# GPU.net
KiCad netlist of a schematic drawn in EAGLE
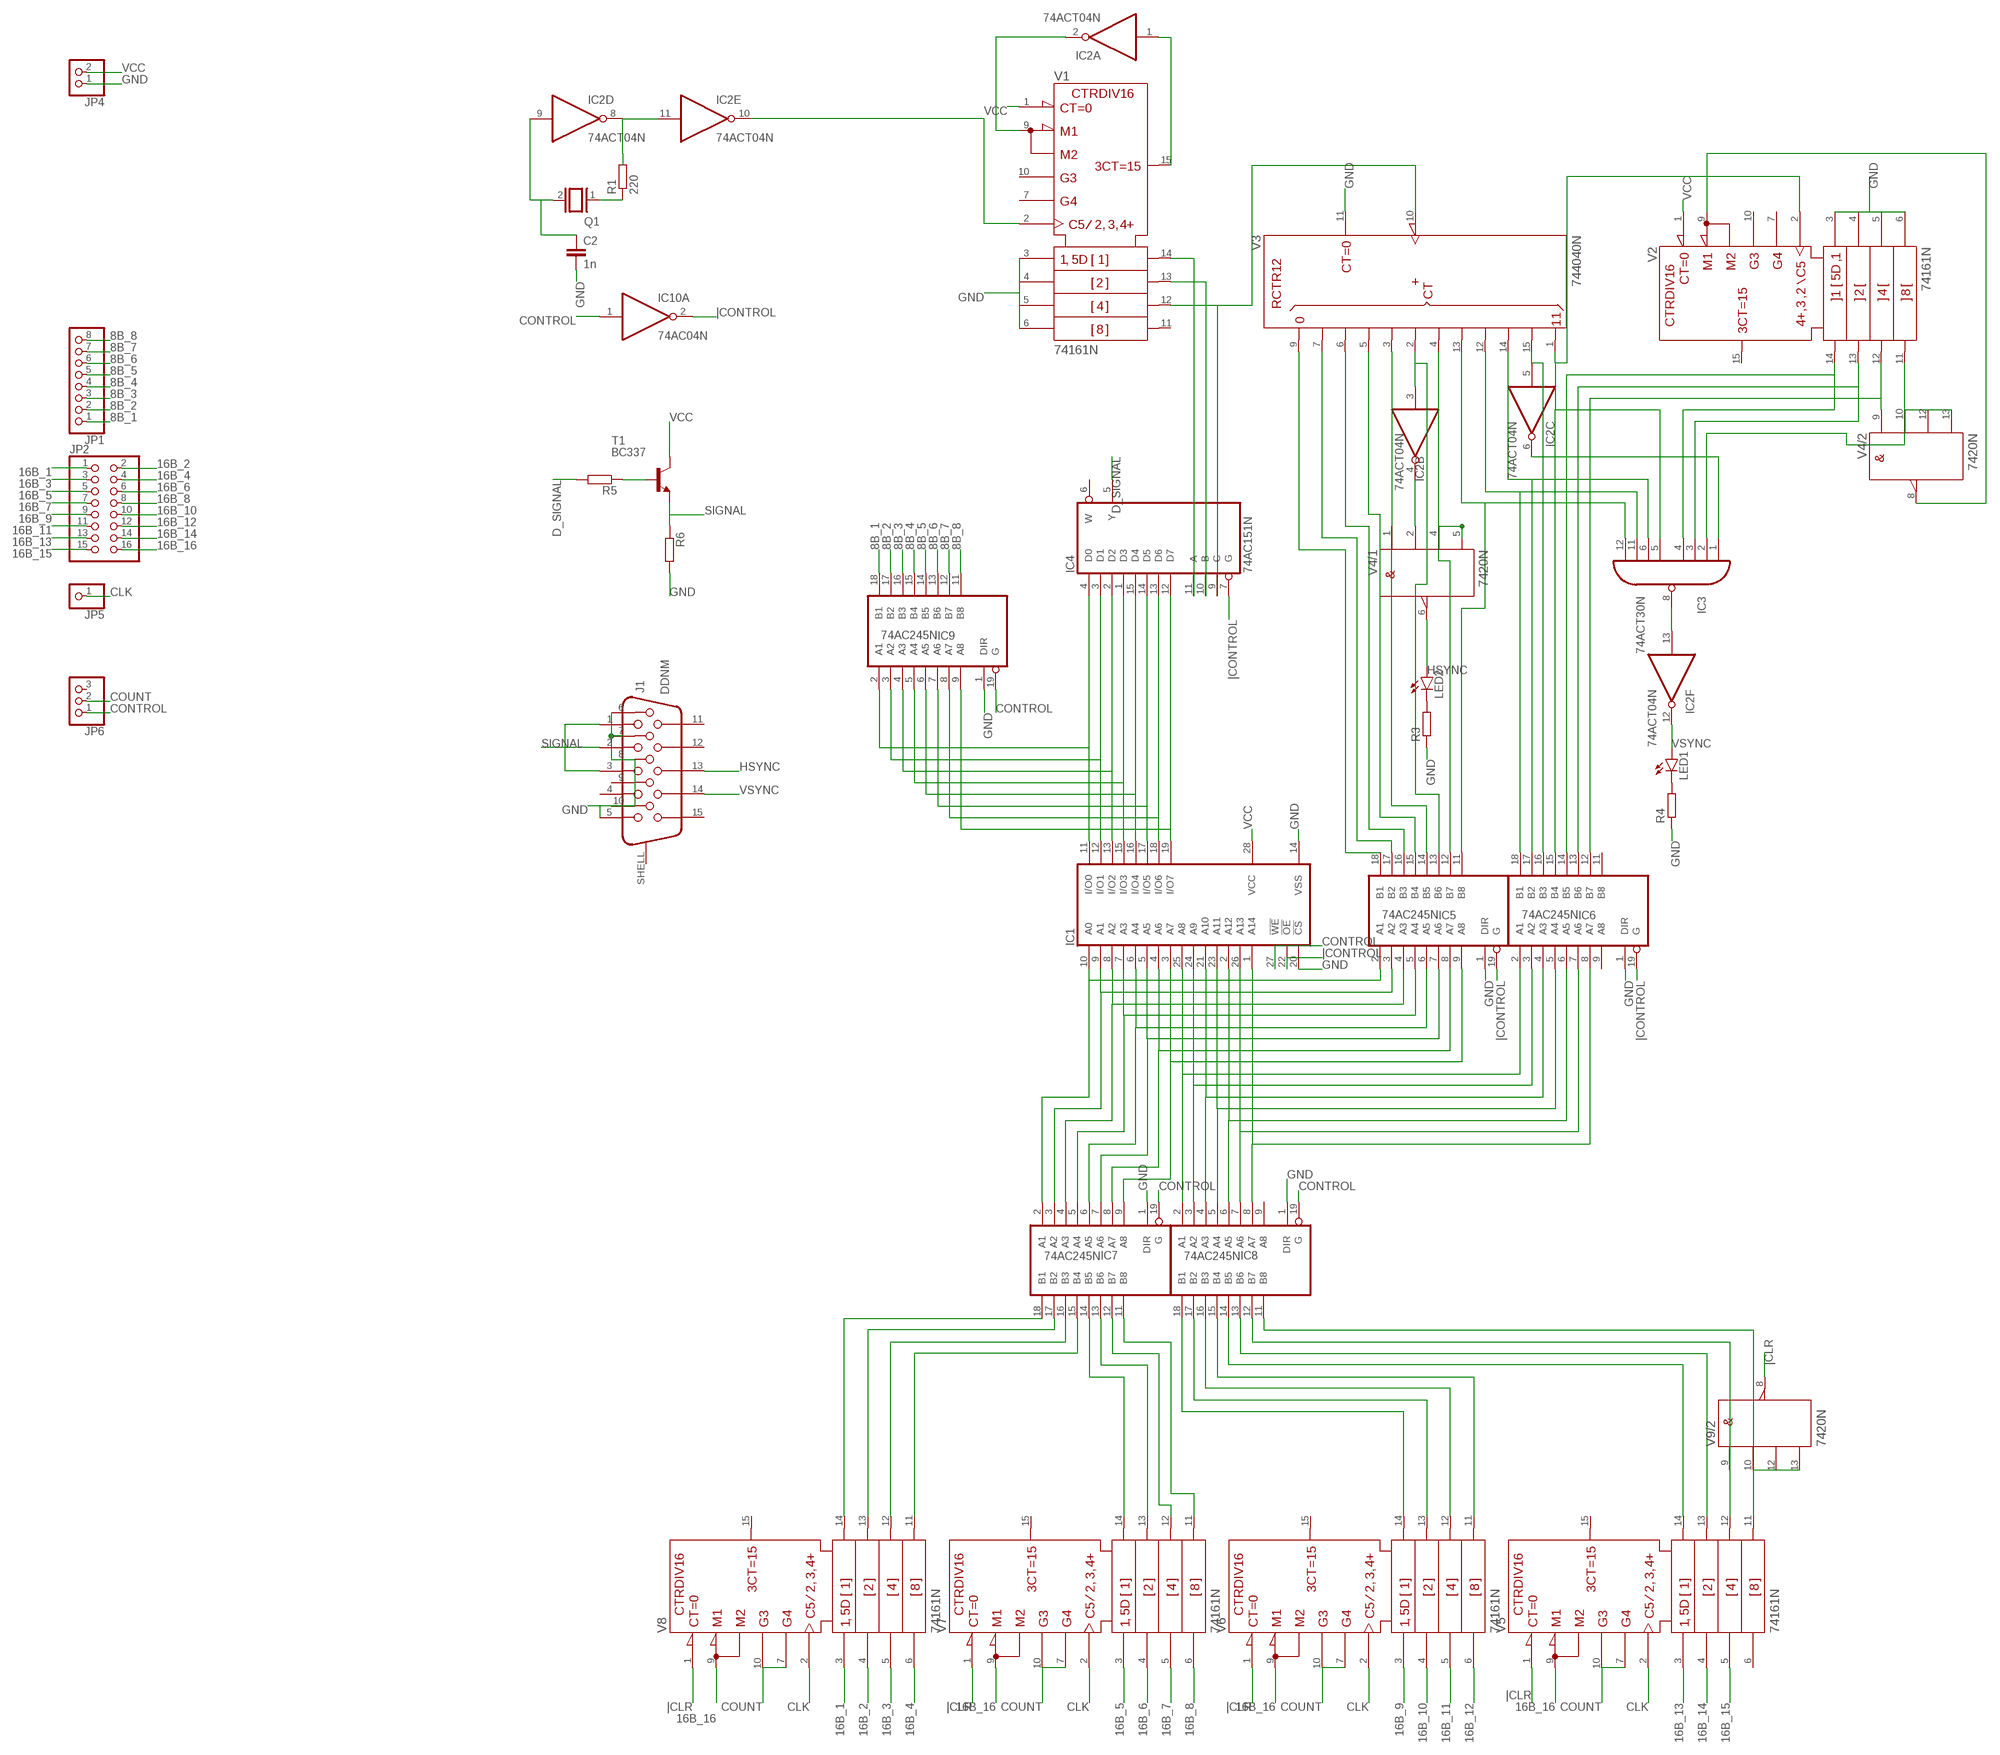
[diagram p0: schematic, sheet 1]

(export (version "E")
  (design (tool "Eeschema 10.0.6"))
  (components
    (comp (ref "C2")
      (value "1n")
      (footprint "eagle-import:C025-025X050")
      (libsource (lib "eagle-import") (part "C-EU025-025X050"))
    )
    (comp (ref "IC1")
      (value "62256P")
      (footprint "eagle-import:DIL28-6")
      (libsource (lib "eagle-import") (part "62256P"))
    )
    (comp (ref "IC2")
      (value "74ACT04N")
      (footprint "eagle-import:DIL14")
      (libsource (lib "eagle-import") (part "7404NACT"))
    )
    (comp (ref "IC3")
      (value "74ACT30N")
      (footprint "eagle-import:DIL14")
      (libsource (lib "eagle-import") (part "7430NACT"))
    )
    (comp (ref "IC4")
      (value "74AC151N")
      (footprint "eagle-import:DIL16")
      (libsource (lib "eagle-import") (part "74151NAC"))
    )
    (comp (ref "IC5")
      (value "74AC245N")
      (footprint "eagle-import:DIL20")
      (libsource (lib "eagle-import") (part "74245NAC"))
    )
    (comp (ref "IC6")
      (value "74AC245N")
      (footprint "eagle-import:DIL20")
      (libsource (lib "eagle-import") (part "74245NAC"))
    )
    (comp (ref "IC7")
      (value "74AC245N")
      (footprint "eagle-import:DIL20")
      (libsource (lib "eagle-import") (part "74245NAC"))
    )
    (comp (ref "IC8")
      (value "74AC245N")
      (footprint "eagle-import:DIL20")
      (libsource (lib "eagle-import") (part "74245NAC"))
    )
    (comp (ref "IC9")
      (value "74AC245N")
      (footprint "eagle-import:DIL20")
      (libsource (lib "eagle-import") (part "74245NAC"))
    )
    (comp (ref "IC10")
      (value "74AC04N")
      (footprint "eagle-import:DIL14")
      (libsource (lib "eagle-import") (part "7404NAC"))
    )
    (comp (ref "J1")
      (value "DDNM")
      (footprint "eagle-import:DNM")
      (fields (field (name "SPICEPREFIX") "X"))
      (libsource (lib "eagle-import") (part "DDNM"))
    )
    (comp (ref "JP1")
      (value "PINHD-1X8")
      (footprint "eagle-import:1X08")
      (libsource (lib "eagle-import") (part "PINHD-1X8"))
    )
    (comp (ref "JP2")
      (value "PINHD-2X8")
      (footprint "eagle-import:2X08")
      (libsource (lib "eagle-import") (part "PINHD-2X8"))
    )
    (comp (ref "JP4")
      (value "PINHD-1X2")
      (footprint "eagle-import:1X02")
      (libsource (lib "eagle-import") (part "PINHD-1X2"))
    )
    (comp (ref "JP5")
      (value "PINHD-1X1")
      (footprint "eagle-import:1X01")
      (libsource (lib "eagle-import") (part "PINHD-1X1"))
    )
    (comp (ref "JP6")
      (value "PINHD-1X3")
      (footprint "eagle-import:1X03")
      (libsource (lib "eagle-import") (part "PINHD-1X3"))
    )
    (comp (ref "LED1")
      (value "LED5MM")
      (footprint "eagle-import:LED5MM")
      (libsource (lib "eagle-import") (part "LED5MM"))
    )
    (comp (ref "LED2")
      (value "LED5MM")
      (footprint "eagle-import:LED5MM")
      (libsource (lib "eagle-import") (part "LED5MM"))
    )
    (comp (ref "Q1")
      (value "XTAL/S")
      (footprint "eagle-import:QS")
      (libsource (lib "eagle-import") (part "XTAL/S"))
    )
    (comp (ref "R1")
      (value "220")
      (footprint "eagle-import:0204_7")
      (libsource (lib "eagle-import") (part "R-EU_0204/7"))
    )
    (comp (ref "R3")
      (value "R-EU_0204/7")
      (footprint "eagle-import:0204_7")
      (libsource (lib "eagle-import") (part "R-EU_0204/7"))
    )
    (comp (ref "R4")
      (value "R-EU_0204/7")
      (footprint "eagle-import:0204_7")
      (libsource (lib "eagle-import") (part "R-EU_0204/7"))
    )
    (comp (ref "R5")
      (value "R-EU_0204/7")
      (footprint "eagle-import:0204_7")
      (libsource (lib "eagle-import") (part "resistor_348_R-EU_0204/7"))
    )
    (comp (ref "R6")
      (value "R-EU_0204/7")
      (footprint "eagle-import:0204_7")
      (libsource (lib "eagle-import") (part "resistor_348_R-EU_0204/7"))
    )
    (comp (ref "T1")
      (value "BC337")
      (footprint "eagle-import:TO92")
      (libsource (lib "eagle-import") (part "BC337"))
    )
    (comp (ref "V1")
      (value "74161N")
      (footprint "eagle-import:DIL16")
      (libsource (lib "eagle-import") (part "74161N"))
    )
    (comp (ref "V2")
      (value "74161N")
      (footprint "eagle-import:DIL16")
      (libsource (lib "eagle-import") (part "74161N"))
    )
    (comp (ref "V3")
      (value "744040N")
      (footprint "eagle-import:DIL16")
      (libsource (lib "eagle-import") (part "744040N"))
    )
    (comp (ref "V4")
      (value "7420N")
      (footprint "eagle-import:DIL14")
      (libsource (lib "eagle-import") (part "7420N"))
    )
    (comp (ref "V5")
      (value "74161N")
      (footprint "eagle-import:DIL16")
      (libsource (lib "eagle-import") (part "74161N"))
    )
    (comp (ref "V6")
      (value "74161N")
      (footprint "eagle-import:DIL16")
      (libsource (lib "eagle-import") (part "74161N"))
    )
    (comp (ref "V7")
      (value "74161N")
      (footprint "eagle-import:DIL16")
      (libsource (lib "eagle-import") (part "74161N"))
    )
    (comp (ref "V8")
      (value "74161N")
      (footprint "eagle-import:DIL16")
      (libsource (lib "eagle-import") (part "74161N"))
    )
    (comp (ref "V9")
      (value "7420N")
      (footprint "eagle-import:DIL14")
      (libsource (lib "eagle-import") (part "7420N"))
    )
  )
  (nets
    (net (code "1") (name "/8B_1") (class "Default")
      (node (ref "IC9") (pin "18") (pinfunction "B1_18") (pintype "bidirectional"))
      (node (ref "JP1") (pin "1") (pinfunction "1_1") (pintype "passive"))
    )
    (net (code "2") (name "/8B_2") (class "Default")
      (node (ref "IC9") (pin "17") (pinfunction "B2_17") (pintype "bidirectional"))
      (node (ref "JP1") (pin "2") (pinfunction "2_2") (pintype "passive"))
    )
    (net (code "3") (name "/8B_3") (class "Default")
      (node (ref "IC9") (pin "16") (pinfunction "B3_16") (pintype "bidirectional"))
      (node (ref "JP1") (pin "3") (pinfunction "3_3") (pintype "passive"))
    )
    (net (code "4") (name "/8B_4") (class "Default")
      (node (ref "IC9") (pin "15") (pinfunction "B4_15") (pintype "bidirectional"))
      (node (ref "JP1") (pin "4") (pinfunction "4_4") (pintype "passive"))
    )
    (net (code "5") (name "/8B_5") (class "Default")
      (node (ref "IC9") (pin "14") (pinfunction "B5_14") (pintype "bidirectional"))
      (node (ref "JP1") (pin "5") (pinfunction "5_5") (pintype "passive"))
    )
    (net (code "6") (name "/8B_6") (class "Default")
      (node (ref "IC9") (pin "13") (pinfunction "B6_13") (pintype "bidirectional"))
      (node (ref "JP1") (pin "6") (pinfunction "6_6") (pintype "passive"))
    )
    (net (code "7") (name "/8B_7") (class "Default")
      (node (ref "IC9") (pin "12") (pinfunction "B7_12") (pintype "bidirectional"))
      (node (ref "JP1") (pin "7") (pinfunction "7_7") (pintype "passive"))
    )
    (net (code "8") (name "/8B_8") (class "Default")
      (node (ref "IC9") (pin "11") (pinfunction "B8_11") (pintype "bidirectional"))
      (node (ref "JP1") (pin "8") (pinfunction "8_8") (pintype "passive"))
    )
    (net (code "9") (name "/16B_1") (class "Default")
      (node (ref "JP2") (pin "1") (pinfunction "1_1") (pintype "passive"))
      (node (ref "V8") (pin "3") (pinfunction "A_3") (pintype "input"))
    )
    (net (code "10") (name "/16B_2") (class "Default")
      (node (ref "JP2") (pin "2") (pinfunction "2_2") (pintype "passive"))
      (node (ref "V8") (pin "4") (pinfunction "B_4") (pintype "input"))
    )
    (net (code "11") (name "/16B_3") (class "Default")
      (node (ref "JP2") (pin "3") (pinfunction "3_3") (pintype "passive"))
      (node (ref "V8") (pin "5") (pinfunction "C_5") (pintype "input"))
    )
    (net (code "12") (name "/16B_4") (class "Default")
      (node (ref "JP2") (pin "4") (pinfunction "4_4") (pintype "passive"))
      (node (ref "V8") (pin "6") (pinfunction "D_6") (pintype "input"))
    )
    (net (code "13") (name "/16B_5") (class "Default")
      (node (ref "JP2") (pin "5") (pinfunction "5_5") (pintype "passive"))
      (node (ref "V7") (pin "3") (pinfunction "A_3") (pintype "input"))
    )
    (net (code "14") (name "/16B_6") (class "Default")
      (node (ref "JP2") (pin "6") (pinfunction "6_6") (pintype "passive"))
      (node (ref "V7") (pin "4") (pinfunction "B_4") (pintype "input"))
    )
    (net (code "15") (name "/16B_7") (class "Default")
      (node (ref "JP2") (pin "7") (pinfunction "7_7") (pintype "passive"))
      (node (ref "V7") (pin "5") (pinfunction "C_5") (pintype "input"))
    )
    (net (code "16") (name "/16B_8") (class "Default")
      (node (ref "JP2") (pin "8") (pinfunction "8_8") (pintype "passive"))
      (node (ref "V7") (pin "6") (pinfunction "D_6") (pintype "input"))
    )
    (net (code "17") (name "/16B_9") (class "Default")
      (node (ref "JP2") (pin "9") (pinfunction "9_9") (pintype "passive"))
      (node (ref "V6") (pin "3") (pinfunction "A_3") (pintype "input"))
    )
    (net (code "18") (name "/16B_10") (class "Default")
      (node (ref "JP2") (pin "10") (pinfunction "10_10") (pintype "passive"))
      (node (ref "V6") (pin "4") (pinfunction "B_4") (pintype "input"))
    )
    (net (code "19") (name "/16B_11") (class "Default")
      (node (ref "JP2") (pin "11") (pinfunction "11_11") (pintype "passive"))
      (node (ref "V6") (pin "5") (pinfunction "C_5") (pintype "input"))
    )
    (net (code "20") (name "/16B_12") (class "Default")
      (node (ref "JP2") (pin "12") (pinfunction "12_12") (pintype "passive"))
      (node (ref "V6") (pin "6") (pinfunction "D_6") (pintype "input"))
    )
    (net (code "21") (name "/16B_13") (class "Default")
      (node (ref "JP2") (pin "13") (pinfunction "13_13") (pintype "passive"))
      (node (ref "V5") (pin "3") (pinfunction "A_3") (pintype "input"))
    )
    (net (code "22") (name "/16B_14") (class "Default")
      (node (ref "JP2") (pin "14") (pinfunction "14_14") (pintype "passive"))
      (node (ref "V5") (pin "4") (pinfunction "B_4") (pintype "input"))
    )
    (net (code "23") (name "/16B_15") (class "Default")
      (node (ref "JP2") (pin "15") (pinfunction "15_15") (pintype "passive"))
      (node (ref "V5") (pin "5") (pinfunction "C_5") (pintype "input"))
    )
    (net (code "24") (name "/16B_16") (class "Default")
      (node (ref "JP2") (pin "16") (pinfunction "16_16") (pintype "passive"))
      (node (ref "V5") (pin "9") (pinfunction "~{LOAD}_9") (pintype "input"))
      (node (ref "V6") (pin "9") (pinfunction "~{LOAD}_9") (pintype "input"))
      (node (ref "V7") (pin "9") (pinfunction "~{LOAD}_9") (pintype "input"))
      (node (ref "V8") (pin "9") (pinfunction "~{LOAD}_9") (pintype "input"))
    )
    (net (code "25") (name "/CLK") (class "Default")
      (node (ref "JP5") (pin "1") (pinfunction "1_1") (pintype "passive"))
      (node (ref "V5") (pin "2") (pinfunction "CLK_2") (pintype "input"))
      (node (ref "V6") (pin "2") (pinfunction "CLK_2") (pintype "input"))
      (node (ref "V7") (pin "2") (pinfunction "CLK_2") (pintype "input"))
      (node (ref "V8") (pin "2") (pinfunction "CLK_2") (pintype "input"))
    )
    (net (code "26") (name "/CONTROL") (class "Default")
      (node (ref "IC1") (pin "27") (pinfunction "~{WE}_27") (pintype "input"))
      (node (ref "IC10") (pin "1") (pinfunction "I_1") (pintype "input"))
      (node (ref "IC7") (pin "19") (pinfunction "G_19") (pintype "input"))
      (node (ref "IC8") (pin "19") (pinfunction "G_19") (pintype "input"))
      (node (ref "IC9") (pin "19") (pinfunction "G_19") (pintype "input"))
      (node (ref "JP6") (pin "1") (pinfunction "1_1") (pintype "passive"))
    )
    (net (code "27") (name "/COUNT") (class "Default")
      (node (ref "JP6") (pin "2") (pinfunction "2_2") (pintype "passive"))
      (node (ref "V5") (pin "10") (pinfunction "ENT_10") (pintype "input"))
      (node (ref "V5") (pin "7") (pinfunction "ENP_7") (pintype "input"))
      (node (ref "V6") (pin "10") (pinfunction "ENT_10") (pintype "input"))
      (node (ref "V6") (pin "7") (pinfunction "ENP_7") (pintype "input"))
      (node (ref "V7") (pin "10") (pinfunction "ENT_10") (pintype "input"))
      (node (ref "V7") (pin "7") (pinfunction "ENP_7") (pintype "input"))
      (node (ref "V8") (pin "10") (pinfunction "ENT_10") (pintype "input"))
      (node (ref "V8") (pin "7") (pinfunction "ENP_7") (pintype "input"))
    )
    (net (code "28") (name "/D_SIGNAL") (class "Default")
      (node (ref "IC4") (pin "5") (pinfunction "Y_5") (pintype "output"))
      (node (ref "R5") (pin "2") (pinfunction "2_2") (pintype "passive"))
    )
    (net (code "29") (name "/GND") (class "Default")
      (node (ref "C2") (pin "2") (pinfunction "2_2") (pintype "passive"))
      (node (ref "IC1") (pin "14") (pinfunction "VSS_14") (pintype "power_in"))
      (node (ref "IC1") (pin "20") (pinfunction "~{CS}_20") (pintype "input"))
      (node (ref "IC5") (pin "1") (pinfunction "DIR_1") (pintype "input"))
      (node (ref "IC6") (pin "1") (pinfunction "DIR_1") (pintype "input"))
      (node (ref "IC7") (pin "1") (pinfunction "DIR_1") (pintype "input"))
      (node (ref "IC8") (pin "1") (pinfunction "DIR_1") (pintype "input"))
      (node (ref "IC9") (pin "1") (pinfunction "DIR_1") (pintype "input"))
      (node (ref "J1") (pin "10") (pinfunction "10_10") (pintype "bidirectional"))
      (node (ref "J1") (pin "5") (pinfunction "5_5") (pintype "bidirectional"))
      (node (ref "J1") (pin "6") (pinfunction "6_6") (pintype "bidirectional"))
      (node (ref "J1") (pin "7") (pinfunction "7_7") (pintype "bidirectional"))
      (node (ref "J1") (pin "8") (pinfunction "8_8") (pintype "bidirectional"))
      (node (ref "JP4") (pin "1") (pinfunction "1_1") (pintype "passive"))
      (node (ref "R3") (pin "1") (pinfunction "1_1") (pintype "passive"))
      (node (ref "R4") (pin "1") (pinfunction "1_1") (pintype "passive"))
      (node (ref "R6") (pin "2") (pinfunction "2_2") (pintype "passive"))
      (node (ref "V1") (pin "3") (pinfunction "A_3") (pintype "input"))
      (node (ref "V1") (pin "4") (pinfunction "B_4") (pintype "input"))
      (node (ref "V1") (pin "5") (pinfunction "C_5") (pintype "input"))
      (node (ref "V1") (pin "6") (pinfunction "D_6") (pintype "input"))
      (node (ref "V2") (pin "3") (pinfunction "A_3") (pintype "input"))
      (node (ref "V2") (pin "4") (pinfunction "B_4") (pintype "input"))
      (node (ref "V2") (pin "5") (pinfunction "C_5") (pintype "input"))
      (node (ref "V2") (pin "6") (pinfunction "D_6") (pintype "input"))
      (node (ref "V3") (pin "11") (pinfunction "CLR_11") (pintype "input"))
    )
    (net (code "30") (name "/HSYNC") (class "Default")
      (node (ref "J1") (pin "13") (pinfunction "13_13") (pintype "bidirectional"))
      (node (ref "LED2") (pin "A") (pinfunction "A_A") (pintype "passive"))
      (node (ref "V4") (pin "6") (pinfunction "Y_6") (pintype "output"))
    )
    (net (code "31") (name "/SIGNAL") (class "Default")
      (node (ref "J1") (pin "1") (pinfunction "1_1") (pintype "bidirectional"))
      (node (ref "J1") (pin "2") (pinfunction "2_2") (pintype "bidirectional"))
      (node (ref "J1") (pin "3") (pinfunction "3_3") (pintype "bidirectional"))
      (node (ref "R6") (pin "1") (pinfunction "1_1") (pintype "passive"))
      (node (ref "T1") (pin "1") (pinfunction "E_1") (pintype "passive"))
    )
    (net (code "32") (name "/VCC") (class "Default")
      (node (ref "IC1") (pin "28") (pinfunction "VCC_28") (pintype "power_in"))
      (node (ref "JP4") (pin "2") (pinfunction "2_2") (pintype "passive"))
      (node (ref "T1") (pin "3") (pinfunction "C_3") (pintype "passive"))
      (node (ref "V1") (pin "1") (pinfunction "~{CLR}_1") (pintype "input"))
      (node (ref "V2") (pin "1") (pinfunction "~{CLR}_1") (pintype "input"))
    )
    (net (code "33") (name "/VSYNC") (class "Default")
      (node (ref "IC2") (pin "12") (pinfunction "O_12") (pintype "output"))
      (node (ref "J1") (pin "14") (pinfunction "14_14") (pintype "bidirectional"))
      (node (ref "LED1") (pin "A") (pinfunction "A_A") (pintype "passive"))
    )
    (net (code "34") (name "/|CLR") (class "Default")
      (node (ref "V5") (pin "1") (pinfunction "~{CLR}_1") (pintype "input"))
      (node (ref "V6") (pin "1") (pinfunction "~{CLR}_1") (pintype "input"))
      (node (ref "V7") (pin "1") (pinfunction "~{CLR}_1") (pintype "input"))
      (node (ref "V8") (pin "1") (pinfunction "~{CLR}_1") (pintype "input"))
      (node (ref "V9") (pin "8") (pinfunction "Y_8") (pintype "output"))
    )
    (net (code "35") (name "/|CONTROL") (class "Default")
      (node (ref "IC1") (pin "22") (pinfunction "~{OE}_22") (pintype "input"))
      (node (ref "IC10") (pin "2") (pinfunction "O_2") (pintype "output"))
      (node (ref "IC4") (pin "7") (pinfunction "G_7") (pintype "input"))
      (node (ref "IC5") (pin "19") (pinfunction "G_19") (pintype "input"))
      (node (ref "IC6") (pin "19") (pinfunction "G_19") (pintype "input"))
    )
    (net (code "36") (name "Net-(IC1-A0)") (class "Default")
      (node (ref "IC1") (pin "10") (pinfunction "A0_10") (pintype "input"))
      (node (ref "IC5") (pin "2") (pinfunction "A1_2") (pintype "bidirectional"))
      (node (ref "IC7") (pin "2") (pinfunction "A1_2") (pintype "bidirectional"))
    )
    (net (code "37") (name "Net-(IC1-A1)") (class "Default")
      (node (ref "IC1") (pin "9") (pinfunction "A1_9") (pintype "input"))
      (node (ref "IC5") (pin "3") (pinfunction "A2_3") (pintype "bidirectional"))
      (node (ref "IC7") (pin "3") (pinfunction "A2_3") (pintype "bidirectional"))
    )
    (net (code "38") (name "Net-(IC1-A2)") (class "Default")
      (node (ref "IC1") (pin "8") (pinfunction "A2_8") (pintype "input"))
      (node (ref "IC5") (pin "4") (pinfunction "A3_4") (pintype "bidirectional"))
      (node (ref "IC7") (pin "4") (pinfunction "A3_4") (pintype "bidirectional"))
    )
    (net (code "39") (name "Net-(IC1-A3)") (class "Default")
      (node (ref "IC1") (pin "7") (pinfunction "A3_7") (pintype "input"))
      (node (ref "IC5") (pin "5") (pinfunction "A4_5") (pintype "bidirectional"))
      (node (ref "IC7") (pin "5") (pinfunction "A4_5") (pintype "bidirectional"))
    )
    (net (code "40") (name "Net-(IC1-A4)") (class "Default")
      (node (ref "IC1") (pin "6") (pinfunction "A4_6") (pintype "input"))
      (node (ref "IC5") (pin "6") (pinfunction "A5_6") (pintype "bidirectional"))
      (node (ref "IC7") (pin "6") (pinfunction "A5_6") (pintype "bidirectional"))
    )
    (net (code "41") (name "Net-(IC1-A5)") (class "Default")
      (node (ref "IC1") (pin "5") (pinfunction "A5_5") (pintype "input"))
      (node (ref "IC5") (pin "7") (pinfunction "A6_7") (pintype "bidirectional"))
      (node (ref "IC7") (pin "7") (pinfunction "A6_7") (pintype "bidirectional"))
    )
    (net (code "42") (name "Net-(IC1-A6)") (class "Default")
      (node (ref "IC1") (pin "4") (pinfunction "A6_4") (pintype "input"))
      (node (ref "IC5") (pin "8") (pinfunction "A7_8") (pintype "bidirectional"))
      (node (ref "IC7") (pin "8") (pinfunction "A7_8") (pintype "bidirectional"))
    )
    (net (code "43") (name "Net-(IC1-A7)") (class "Default")
      (node (ref "IC1") (pin "3") (pinfunction "A7_3") (pintype "input"))
      (node (ref "IC5") (pin "9") (pinfunction "A8_9") (pintype "bidirectional"))
      (node (ref "IC7") (pin "9") (pinfunction "A8_9") (pintype "bidirectional"))
    )
    (net (code "44") (name "Net-(IC1-A8)") (class "Default")
      (node (ref "IC1") (pin "25") (pinfunction "A8_25") (pintype "input"))
      (node (ref "IC6") (pin "2") (pinfunction "A1_2") (pintype "bidirectional"))
      (node (ref "IC8") (pin "2") (pinfunction "A1_2") (pintype "bidirectional"))
    )
    (net (code "45") (name "Net-(IC1-A9)") (class "Default")
      (node (ref "IC1") (pin "24") (pinfunction "A9_24") (pintype "input"))
      (node (ref "IC6") (pin "3") (pinfunction "A2_3") (pintype "bidirectional"))
      (node (ref "IC8") (pin "3") (pinfunction "A2_3") (pintype "bidirectional"))
    )
    (net (code "46") (name "Net-(IC1-A10)") (class "Default")
      (node (ref "IC1") (pin "21") (pinfunction "A10_21") (pintype "input"))
      (node (ref "IC6") (pin "4") (pinfunction "A3_4") (pintype "bidirectional"))
      (node (ref "IC8") (pin "4") (pinfunction "A3_4") (pintype "bidirectional"))
    )
    (net (code "47") (name "Net-(IC1-A11)") (class "Default")
      (node (ref "IC1") (pin "23") (pinfunction "A11_23") (pintype "input"))
      (node (ref "IC6") (pin "5") (pinfunction "A4_5") (pintype "bidirectional"))
      (node (ref "IC8") (pin "5") (pinfunction "A4_5") (pintype "bidirectional"))
    )
    (net (code "48") (name "Net-(IC1-A12)") (class "Default")
      (node (ref "IC1") (pin "2") (pinfunction "A12_2") (pintype "input"))
      (node (ref "IC6") (pin "6") (pinfunction "A5_6") (pintype "bidirectional"))
      (node (ref "IC8") (pin "6") (pinfunction "A5_6") (pintype "bidirectional"))
    )
    (net (code "49") (name "Net-(IC1-A13)") (class "Default")
      (node (ref "IC1") (pin "26") (pinfunction "A13_26") (pintype "input"))
      (node (ref "IC6") (pin "7") (pinfunction "A6_7") (pintype "bidirectional"))
      (node (ref "IC8") (pin "7") (pinfunction "A6_7") (pintype "bidirectional"))
    )
    (net (code "50") (name "Net-(IC1-A14)") (class "Default")
      (node (ref "IC1") (pin "1") (pinfunction "A14_1") (pintype "input"))
      (node (ref "IC6") (pin "8") (pinfunction "A7_8") (pintype "bidirectional"))
      (node (ref "IC8") (pin "8") (pinfunction "A7_8") (pintype "bidirectional"))
    )
    (net (code "51") (name "Net-(IC1-I{slash}O0)") (class "Default")
      (node (ref "IC1") (pin "11") (pinfunction "I/O0_11") (pintype "bidirectional"))
      (node (ref "IC4") (pin "4") (pinfunction "D0_4") (pintype "input"))
      (node (ref "IC9") (pin "2") (pinfunction "A1_2") (pintype "bidirectional"))
    )
    (net (code "52") (name "Net-(IC1-I{slash}O1)") (class "Default")
      (node (ref "IC1") (pin "12") (pinfunction "I/O1_12") (pintype "bidirectional"))
      (node (ref "IC4") (pin "3") (pinfunction "D1_3") (pintype "input"))
      (node (ref "IC9") (pin "3") (pinfunction "A2_3") (pintype "bidirectional"))
    )
    (net (code "53") (name "Net-(IC1-I{slash}O2)") (class "Default")
      (node (ref "IC1") (pin "13") (pinfunction "I/O2_13") (pintype "bidirectional"))
      (node (ref "IC4") (pin "2") (pinfunction "D2_2") (pintype "input"))
      (node (ref "IC9") (pin "4") (pinfunction "A3_4") (pintype "bidirectional"))
    )
    (net (code "54") (name "Net-(IC1-I{slash}O3)") (class "Default")
      (node (ref "IC1") (pin "15") (pinfunction "I/O3_15") (pintype "bidirectional"))
      (node (ref "IC4") (pin "1") (pinfunction "D3_1") (pintype "input"))
      (node (ref "IC9") (pin "5") (pinfunction "A4_5") (pintype "bidirectional"))
    )
    (net (code "55") (name "Net-(IC1-I{slash}O4)") (class "Default")
      (node (ref "IC1") (pin "16") (pinfunction "I/O4_16") (pintype "bidirectional"))
      (node (ref "IC4") (pin "15") (pinfunction "D4_15") (pintype "input"))
      (node (ref "IC9") (pin "6") (pinfunction "A5_6") (pintype "bidirectional"))
    )
    (net (code "56") (name "Net-(IC1-I{slash}O5)") (class "Default")
      (node (ref "IC1") (pin "17") (pinfunction "I/O5_17") (pintype "bidirectional"))
      (node (ref "IC4") (pin "14") (pinfunction "D5_14") (pintype "input"))
      (node (ref "IC9") (pin "7") (pinfunction "A6_7") (pintype "bidirectional"))
    )
    (net (code "57") (name "Net-(IC1-I{slash}O6)") (class "Default")
      (node (ref "IC1") (pin "18") (pinfunction "I/O6_18") (pintype "bidirectional"))
      (node (ref "IC4") (pin "13") (pinfunction "D6_13") (pintype "input"))
      (node (ref "IC9") (pin "8") (pinfunction "A7_8") (pintype "bidirectional"))
    )
    (net (code "58") (name "Net-(IC1-I{slash}O7)") (class "Default")
      (node (ref "IC1") (pin "19") (pinfunction "I/O7_19") (pintype "bidirectional"))
      (node (ref "IC4") (pin "12") (pinfunction "D7_12") (pintype "input"))
      (node (ref "IC9") (pin "9") (pinfunction "A8_9") (pintype "bidirectional"))
    )
    (net (code "59") (name "Net-(IC2A-I)") (class "Default")
      (node (ref "IC2") (pin "1") (pinfunction "I_1") (pintype "input"))
      (node (ref "V1") (pin "15") (pinfunction "RCO_15") (pintype "output"))
    )
    (net (code "60") (name "Net-(IC2A-O)") (class "Default")
      (node (ref "IC2") (pin "2") (pinfunction "O_2") (pintype "output"))
      (node (ref "V1") (pin "9") (pinfunction "~{LOAD}_9") (pintype "input"))
    )
    (net (code "61") (name "Net-(IC2B-I)") (class "Default")
      (node (ref "IC2") (pin "3") (pinfunction "I_3") (pintype "input"))
      (node (ref "IC5") (pin "13") (pinfunction "B6_13") (pintype "bidirectional"))
      (node (ref "V3") (pin "2") (pinfunction "QF_2") (pintype "output"))
    )
    (net (code "62") (name "Net-(IC2B-O)") (class "Default")
      (node (ref "IC2") (pin "4") (pinfunction "O_4") (pintype "output"))
      (node (ref "V4") (pin "2") (pinfunction "B_2") (pintype "input"))
    )
    (net (code "63") (name "Net-(IC2C-I)") (class "Default")
      (node (ref "IC2") (pin "5") (pinfunction "I_5") (pintype "input"))
      (node (ref "IC6") (pin "16") (pinfunction "B3_16") (pintype "bidirectional"))
      (node (ref "V3") (pin "15") (pinfunction "QK_15") (pintype "output"))
    )
    (net (code "64") (name "Net-(IC2C-O)") (class "Default")
      (node (ref "IC2") (pin "6") (pinfunction "O_6") (pintype "output"))
      (node (ref "IC3") (pin "1") (pinfunction "I0_1") (pintype "input"))
    )
    (net (code "65") (name "Net-(IC2D-I)") (class "Default")
      (node (ref "C2") (pin "1") (pinfunction "1_1") (pintype "passive"))
      (node (ref "IC2") (pin "9") (pinfunction "I_9") (pintype "input"))
      (node (ref "Q1") (pin "2") (pinfunction "2_2") (pintype "passive"))
    )
    (net (code "66") (name "Net-(IC2D-O)") (class "Default")
      (node (ref "IC2") (pin "11") (pinfunction "I_11") (pintype "input"))
      (node (ref "IC2") (pin "8") (pinfunction "O_8") (pintype "output"))
      (node (ref "R1") (pin "2") (pinfunction "2_2") (pintype "passive"))
    )
    (net (code "67") (name "Net-(IC2E-O)") (class "Default")
      (node (ref "IC2") (pin "10") (pinfunction "O_10") (pintype "output"))
      (node (ref "V1") (pin "2") (pinfunction "CLK_2") (pintype "input"))
    )
    (net (code "68") (name "Net-(IC2F-I)") (class "Default")
      (node (ref "IC2") (pin "13") (pinfunction "I_13") (pintype "input"))
      (node (ref "IC3") (pin "8") (pinfunction "O_8") (pintype "output"))
    )
    (net (code "69") (name "Net-(IC3A-I1)") (class "Default")
      (node (ref "IC3") (pin "2") (pinfunction "I1_2") (pintype "input"))
      (node (ref "V2") (pin "11") (pinfunction "QD_11") (pintype "output"))
      (node (ref "V4") (pin "10") (pinfunction "B_10") (pintype "input"))
      (node (ref "V4") (pin "12") (pinfunction "C_12") (pintype "input"))
      (node (ref "V4") (pin "13") (pinfunction "D_13") (pintype "input"))
    )
    (net (code "70") (name "Net-(IC3A-I2)") (class "Default")
      (node (ref "IC3") (pin "3") (pinfunction "I2_3") (pintype "input"))
      (node (ref "IC6") (pin "13") (pinfunction "B6_13") (pintype "bidirectional"))
      (node (ref "V2") (pin "13") (pinfunction "QB_13") (pintype "output"))
    )
    (net (code "71") (name "Net-(IC3A-I3)") (class "Default")
      (node (ref "IC3") (pin "4") (pinfunction "I3_4") (pintype "input"))
      (node (ref "IC6") (pin "14") (pinfunction "B5_14") (pintype "bidirectional"))
      (node (ref "V2") (pin "14") (pinfunction "QA_14") (pintype "output"))
    )
    (net (code "72") (name "Net-(IC3A-I4)") (class "Default")
      (node (ref "IC3") (pin "5") (pinfunction "I4_5") (pintype "input"))
      (node (ref "IC6") (pin "15") (pinfunction "B4_15") (pintype "bidirectional"))
      (node (ref "V2") (pin "2") (pinfunction "CLK_2") (pintype "input"))
      (node (ref "V3") (pin "1") (pinfunction "QL_1") (pintype "output"))
    )
    (net (code "73") (name "Net-(IC3A-I5)") (class "Default")
      (node (ref "IC3") (pin "6") (pinfunction "I5_6") (pintype "input"))
      (node (ref "IC6") (pin "17") (pinfunction "B2_17") (pintype "bidirectional"))
      (node (ref "V3") (pin "14") (pinfunction "QJ_14") (pintype "output"))
    )
    (net (code "74") (name "Net-(IC3A-I6)") (class "Default")
      (node (ref "IC3") (pin "11") (pinfunction "I6_11") (pintype "input"))
      (node (ref "IC6") (pin "18") (pinfunction "B1_18") (pintype "bidirectional"))
      (node (ref "V3") (pin "12") (pinfunction "QI_12") (pintype "output"))
    )
    (net (code "75") (name "Net-(IC3A-I7)") (class "Default")
      (node (ref "IC3") (pin "12") (pinfunction "I7_12") (pintype "input"))
      (node (ref "IC5") (pin "11") (pinfunction "B8_11") (pintype "bidirectional"))
      (node (ref "V3") (pin "13") (pinfunction "QH_13") (pintype "output"))
    )
    (net (code "76") (name "Net-(IC4A-A)") (class "Default")
      (node (ref "IC4") (pin "11") (pinfunction "A_11") (pintype "input"))
      (node (ref "V1") (pin "14") (pinfunction "QA_14") (pintype "output"))
    )
    (net (code "77") (name "Net-(IC4A-B)") (class "Default")
      (node (ref "IC4") (pin "10") (pinfunction "B_10") (pintype "input"))
      (node (ref "V1") (pin "13") (pinfunction "QB_13") (pintype "output"))
    )
    (net (code "78") (name "Net-(IC4A-C)") (class "Default")
      (node (ref "IC4") (pin "9") (pinfunction "C_9") (pintype "input"))
      (node (ref "V1") (pin "12") (pinfunction "QC_12") (pintype "output"))
      (node (ref "V3") (pin "10") (pinfunction "CLK_10") (pintype "input"))
    )
    (net (code "79") (name "Net-(IC5A-B1)") (class "Default")
      (node (ref "IC5") (pin "18") (pinfunction "B1_18") (pintype "bidirectional"))
      (node (ref "V3") (pin "9") (pinfunction "QA_9") (pintype "output"))
    )
    (net (code "80") (name "Net-(IC5A-B2)") (class "Default")
      (node (ref "IC5") (pin "17") (pinfunction "B2_17") (pintype "bidirectional"))
      (node (ref "V3") (pin "7") (pinfunction "QB_7") (pintype "output"))
    )
    (net (code "81") (name "Net-(IC5A-B3)") (class "Default")
      (node (ref "IC5") (pin "16") (pinfunction "B3_16") (pintype "bidirectional"))
      (node (ref "V3") (pin "6") (pinfunction "QC_6") (pintype "output"))
    )
    (net (code "82") (name "Net-(IC5A-B4)") (class "Default")
      (node (ref "IC5") (pin "15") (pinfunction "B4_15") (pintype "bidirectional"))
      (node (ref "V3") (pin "5") (pinfunction "QD_5") (pintype "output"))
    )
    (net (code "83") (name "Net-(IC5A-B5)") (class "Default")
      (node (ref "IC5") (pin "14") (pinfunction "B5_14") (pintype "bidirectional"))
      (node (ref "V3") (pin "3") (pinfunction "QE_3") (pintype "output"))
      (node (ref "V4") (pin "1") (pinfunction "A_1") (pintype "input"))
    )
    (net (code "84") (name "Net-(IC5A-B7)") (class "Default")
      (node (ref "IC5") (pin "12") (pinfunction "B7_12") (pintype "bidirectional"))
      (node (ref "V3") (pin "4") (pinfunction "QG_4") (pintype "output"))
      (node (ref "V4") (pin "4") (pinfunction "C_4") (pintype "input"))
      (node (ref "V4") (pin "5") (pinfunction "D_5") (pintype "input"))
    )
    (net (code "85") (name "Net-(IC6A-B7)") (class "Default")
      (node (ref "IC6") (pin "12") (pinfunction "B7_12") (pintype "bidirectional"))
      (node (ref "V2") (pin "12") (pinfunction "QC_12") (pintype "output"))
      (node (ref "V4") (pin "9") (pinfunction "A_9") (pintype "input"))
    )
    (net (code "86") (name "Net-(IC7A-B1)") (class "Default")
      (node (ref "IC7") (pin "18") (pinfunction "B1_18") (pintype "bidirectional"))
      (node (ref "V8") (pin "14") (pinfunction "QA_14") (pintype "output"))
    )
    (net (code "87") (name "Net-(IC7A-B2)") (class "Default")
      (node (ref "IC7") (pin "17") (pinfunction "B2_17") (pintype "bidirectional"))
      (node (ref "V8") (pin "13") (pinfunction "QB_13") (pintype "output"))
    )
    (net (code "88") (name "Net-(IC7A-B3)") (class "Default")
      (node (ref "IC7") (pin "16") (pinfunction "B3_16") (pintype "bidirectional"))
      (node (ref "V8") (pin "12") (pinfunction "QC_12") (pintype "output"))
    )
    (net (code "89") (name "Net-(IC7A-B4)") (class "Default")
      (node (ref "IC7") (pin "15") (pinfunction "B4_15") (pintype "bidirectional"))
      (node (ref "V8") (pin "11") (pinfunction "QD_11") (pintype "output"))
    )
    (net (code "90") (name "Net-(IC7A-B5)") (class "Default")
      (node (ref "IC7") (pin "14") (pinfunction "B5_14") (pintype "bidirectional"))
      (node (ref "V7") (pin "14") (pinfunction "QA_14") (pintype "output"))
    )
    (net (code "91") (name "Net-(IC7A-B6)") (class "Default")
      (node (ref "IC7") (pin "13") (pinfunction "B6_13") (pintype "bidirectional"))
      (node (ref "V7") (pin "13") (pinfunction "QB_13") (pintype "output"))
    )
    (net (code "92") (name "Net-(IC7A-B7)") (class "Default")
      (node (ref "IC7") (pin "12") (pinfunction "B7_12") (pintype "bidirectional"))
      (node (ref "V7") (pin "12") (pinfunction "QC_12") (pintype "output"))
    )
    (net (code "93") (name "Net-(IC7A-B8)") (class "Default")
      (node (ref "IC7") (pin "11") (pinfunction "B8_11") (pintype "bidirectional"))
      (node (ref "V7") (pin "11") (pinfunction "QD_11") (pintype "output"))
    )
    (net (code "94") (name "Net-(IC8A-B1)") (class "Default")
      (node (ref "IC8") (pin "18") (pinfunction "B1_18") (pintype "bidirectional"))
      (node (ref "V6") (pin "14") (pinfunction "QA_14") (pintype "output"))
    )
    (net (code "95") (name "Net-(IC8A-B2)") (class "Default")
      (node (ref "IC8") (pin "17") (pinfunction "B2_17") (pintype "bidirectional"))
      (node (ref "V6") (pin "13") (pinfunction "QB_13") (pintype "output"))
    )
    (net (code "96") (name "Net-(IC8A-B3)") (class "Default")
      (node (ref "IC8") (pin "16") (pinfunction "B3_16") (pintype "bidirectional"))
      (node (ref "V6") (pin "12") (pinfunction "QC_12") (pintype "output"))
    )
    (net (code "97") (name "Net-(IC8A-B4)") (class "Default")
      (node (ref "IC8") (pin "15") (pinfunction "B4_15") (pintype "bidirectional"))
      (node (ref "V6") (pin "11") (pinfunction "QD_11") (pintype "output"))
    )
    (net (code "98") (name "Net-(IC8A-B5)") (class "Default")
      (node (ref "IC8") (pin "14") (pinfunction "B5_14") (pintype "bidirectional"))
      (node (ref "V5") (pin "14") (pinfunction "QA_14") (pintype "output"))
    )
    (net (code "99") (name "Net-(IC8A-B6)") (class "Default")
      (node (ref "IC8") (pin "13") (pinfunction "B6_13") (pintype "bidirectional"))
      (node (ref "V5") (pin "13") (pinfunction "QB_13") (pintype "output"))
    )
    (net (code "100") (name "Net-(IC8A-B7)") (class "Default")
      (node (ref "IC8") (pin "12") (pinfunction "B7_12") (pintype "bidirectional"))
      (node (ref "V5") (pin "12") (pinfunction "QC_12") (pintype "output"))
      (node (ref "V9") (pin "9") (pinfunction "A_9") (pintype "input"))
    )
    (net (code "101") (name "Net-(IC8A-B8)") (class "Default")
      (node (ref "IC8") (pin "11") (pinfunction "B8_11") (pintype "bidirectional"))
      (node (ref "V5") (pin "11") (pinfunction "QD_11") (pintype "output"))
      (node (ref "V9") (pin "10") (pinfunction "B_10") (pintype "input"))
      (node (ref "V9") (pin "12") (pinfunction "C_12") (pintype "input"))
      (node (ref "V9") (pin "13") (pinfunction "D_13") (pintype "input"))
    )
    (net (code "102") (name "Net-(LED1-C)") (class "Default")
      (node (ref "LED1") (pin "K") (pinfunction "C_K") (pintype "passive"))
      (node (ref "R4") (pin "2") (pinfunction "2_2") (pintype "passive"))
    )
    (net (code "103") (name "Net-(LED2-C)") (class "Default")
      (node (ref "LED2") (pin "K") (pinfunction "C_K") (pintype "passive"))
      (node (ref "R3") (pin "2") (pinfunction "2_2") (pintype "passive"))
    )
    (net (code "104") (name "Net-(Q1-Pad1)") (class "Default")
      (node (ref "Q1") (pin "1") (pinfunction "1_1") (pintype "passive"))
      (node (ref "R1") (pin "1") (pinfunction "1_1") (pintype "passive"))
    )
    (net (code "105") (name "Net-(T1-B)") (class "Default")
      (node (ref "R5") (pin "1") (pinfunction "1_1") (pintype "passive"))
      (node (ref "T1") (pin "2") (pinfunction "B_2") (pintype "passive"))
    )
    (net (code "106") (name "Net-(V2C-~{LOAD})") (class "Default")
      (node (ref "V2") (pin "9") (pinfunction "~{LOAD}_9") (pintype "input"))
      (node (ref "V4") (pin "8") (pinfunction "Y_8") (pintype "output"))
    )
    (net (code "107") (name "unconnected-(IC4A-W-Pad6)") (class "Default")
      (node (ref "IC4") (pin "6") (pinfunction "W_6") (pintype "output"))
    )
    (net (code "108") (name "unconnected-(IC6A-A8-Pad9)") (class "Default")
      (node (ref "IC6") (pin "9") (pinfunction "A8_9") (pintype "bidirectional"))
    )
    (net (code "109") (name "unconnected-(IC6A-B8-Pad11)") (class "Default")
      (node (ref "IC6") (pin "11") (pinfunction "B8_11") (pintype "bidirectional"))
    )
    (net (code "110") (name "unconnected-(IC8A-A8-Pad9)") (class "Default")
      (node (ref "IC8") (pin "9") (pinfunction "A8_9") (pintype "bidirectional"))
    )
    (net (code "111") (name "unconnected-(J1-Pad4)") (class "Default")
      (node (ref "J1") (pin "4") (pinfunction "4_4") (pintype "bidirectional"))
    )
    (net (code "112") (name "unconnected-(J1-Pad9)") (class "Default")
      (node (ref "J1") (pin "9") (pinfunction "9_9") (pintype "bidirectional"))
    )
    (net (code "113") (name "unconnected-(J1-Pad11)") (class "Default")
      (node (ref "J1") (pin "11") (pinfunction "11_11") (pintype "bidirectional"))
    )
    (net (code "114") (name "unconnected-(J1-Pad12)") (class "Default")
      (node (ref "J1") (pin "12") (pinfunction "12_12") (pintype "bidirectional"))
    )
    (net (code "115") (name "unconnected-(J1-Pad15)") (class "Default")
      (node (ref "J1") (pin "15") (pinfunction "15_15") (pintype "bidirectional"))
    )
    (net (code "116") (name "unconnected-(J1-SHIELD-PadSHELL)") (class "Default")
      (node (ref "J1") (pin "SHELL") (pinfunction "SHIELD_SHELL") (pintype "bidirectional"))
    )
    (net (code "117") (name "unconnected-(JP6-Pad3)") (class "Default")
      (node (ref "JP6") (pin "3") (pinfunction "3_3") (pintype "passive"))
    )
    (net (code "118") (name "unconnected-(V1C-ENP-Pad7)") (class "Default")
      (node (ref "V1") (pin "7") (pinfunction "ENP_7") (pintype "input"))
    )
    (net (code "119") (name "unconnected-(V1C-ENT-Pad10)") (class "Default")
      (node (ref "V1") (pin "10") (pinfunction "ENT_10") (pintype "input"))
    )
    (net (code "120") (name "unconnected-(V1C-QD-Pad11)") (class "Default")
      (node (ref "V1") (pin "11") (pinfunction "QD_11") (pintype "output"))
    )
    (net (code "121") (name "unconnected-(V2C-ENP-Pad7)") (class "Default")
      (node (ref "V2") (pin "7") (pinfunction "ENP_7") (pintype "input"))
    )
    (net (code "122") (name "unconnected-(V2C-ENT-Pad10)") (class "Default")
      (node (ref "V2") (pin "10") (pinfunction "ENT_10") (pintype "input"))
    )
    (net (code "123") (name "unconnected-(V2C-RCO-Pad15)") (class "Default")
      (node (ref "V2") (pin "15") (pinfunction "RCO_15") (pintype "output"))
    )
    (net (code "124") (name "unconnected-(V5C-D-Pad6)") (class "Default")
      (node (ref "V5") (pin "6") (pinfunction "D_6") (pintype "input"))
    )
    (net (code "125") (name "unconnected-(V5C-RCO-Pad15)") (class "Default")
      (node (ref "V5") (pin "15") (pinfunction "RCO_15") (pintype "output"))
    )
    (net (code "126") (name "unconnected-(V6C-RCO-Pad15)") (class "Default")
      (node (ref "V6") (pin "15") (pinfunction "RCO_15") (pintype "output"))
    )
    (net (code "127") (name "unconnected-(V7C-RCO-Pad15)") (class "Default")
      (node (ref "V7") (pin "15") (pinfunction "RCO_15") (pintype "output"))
    )
    (net (code "128") (name "unconnected-(V8C-RCO-Pad15)") (class "Default")
      (node (ref "V8") (pin "15") (pinfunction "RCO_15") (pintype "output"))
    )
  )
)
